# Sensing_-_Position.net
KiCad netlist of a schematic drawn in Altium Designer
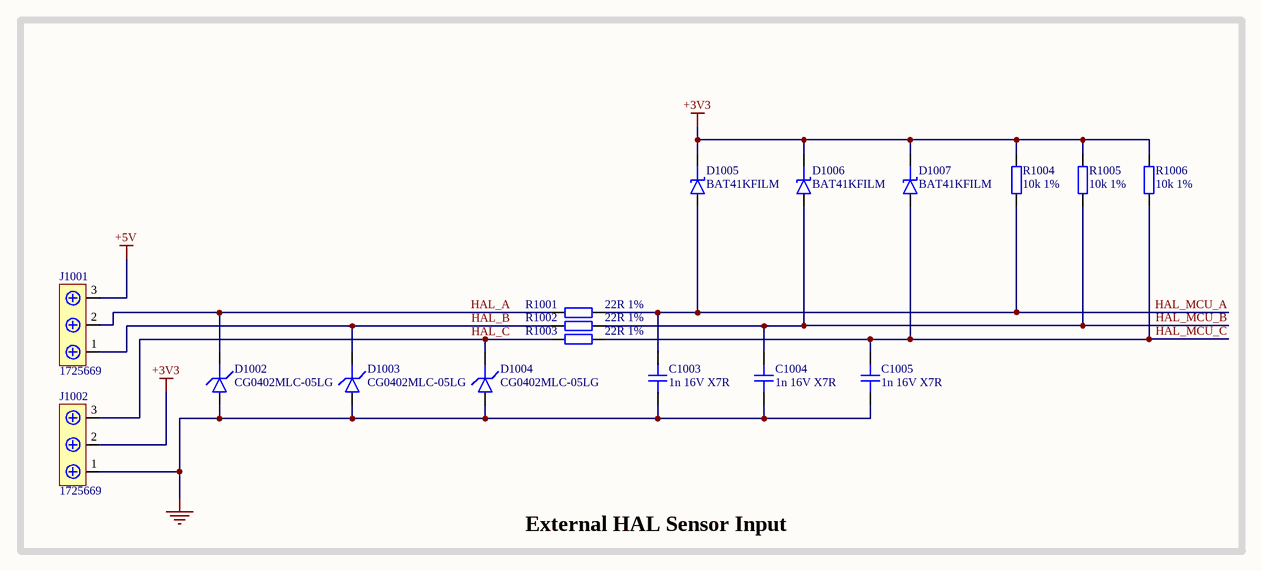
[diagram p0: Sensing - Position.SchDoc]

(export (version "E")
  (design (tool "Eeschema 10.0.6"))
  (components
    (comp (ref "C1003")
      (value "1n 16V X7R")
      (footprint "CAP_0402")
      (description "Capacitor SMD 0402")
      (fields
        (field (name "MANUFACTURER") "YAGEO")
        (field (name "MANUFACTURER PART NUMBER") "CC0402KRX7R7BB102")
      )
      (libsource (lib "Schematic-Lib-PhilsLab") (part "CAP_0402"))
    )
    (comp (ref "C1004")
      (value "1n 16V X7R")
      (footprint "CAP_0402")
      (description "Capacitor SMD 0402")
      (fields
        (field (name "MANUFACTURER") "YAGEO")
        (field (name "MANUFACTURER PART NUMBER") "CC0402KRX7R7BB102")
      )
      (libsource (lib "Schematic-Lib-PhilsLab") (part "CAP_0402"))
    )
    (comp (ref "C1005")
      (value "1n 16V X7R")
      (footprint "CAP_0402")
      (description "Capacitor SMD 0402")
      (fields
        (field (name "MANUFACTURER") "YAGEO")
        (field (name "MANUFACTURER PART NUMBER") "CC0402KRX7R7BB102")
      )
      (libsource (lib "Schematic-Lib-PhilsLab") (part "CAP_0402"))
    )
    (comp (ref "D1002")
      (value "CG0402MLC-05LG")
      (footprint "D_0402")
      (description "Diode TVS / ESD 0402")
      (fields (field (name "MANUFACTURER") "BOURNS"))
      (libsource (lib "Schematic-Lib-PhilsLab") (part "D_TVS_0402"))
    )
    (comp (ref "D1003")
      (value "CG0402MLC-05LG")
      (footprint "D_0402")
      (description "Diode TVS / ESD 0402")
      (libsource (lib "Schematic-Lib-PhilsLab") (part "D_TVS_0402"))
    )
    (comp (ref "D1004")
      (value "CG0402MLC-05LG")
      (footprint "D_0402")
      (description "Diode TVS / ESD 0402")
      (libsource (lib "Schematic-Lib-PhilsLab") (part "D_TVS_0402"))
    )
    (comp (ref "D1005")
      (value "BAT41KFILM")
      (footprint "SOD-523")
      (description "Diode Schottky SMD SOD-323")
      (fields (field (name "MANUFACTURER") "STMicroelectronics"))
      (libsource (lib "Schematic-Lib-PhilsLab") (part "D_SCHOTTKY_SOD_523"))
    )
    (comp (ref "D1006")
      (value "BAT41KFILM")
      (footprint "SOD-523")
      (description "Diode Schottky SMD SOD-323")
      (fields (field (name "MANUFACTURER") "STMicroelectronics"))
      (libsource (lib "Schematic-Lib-PhilsLab") (part "D_SCHOTTKY_SOD_523"))
    )
    (comp (ref "D1007")
      (value "BAT41KFILM")
      (footprint "SOD-523")
      (description "Diode Schottky SMD SOD-323")
      (fields (field (name "MANUFACTURER") "STMicroelectronics"))
      (libsource (lib "Schematic-Lib-PhilsLab") (part "D_SCHOTTKY_SOD_523"))
    )
    (comp (ref "J1001")
      (value "1725669")
      (footprint "1725669")
      (description "Screw Terminal Block 3 Positions 2.54mm")
      (fields (field (name "MANUFACTURER") "Phoenix"))
      (libsource (lib "Schematic-Lib") (part "1725669"))
    )
    (comp (ref "J1002")
      (value "1725669")
      (footprint "1725669")
      (description "Screw Terminal Block 3 Positions 2.54mm")
      (fields (field (name "MANUFACTURER") "Phoenix"))
      (libsource (lib "Schematic-Lib") (part "1725669"))
    )
    (comp (ref "R1001")
      (value "22R 1%")
      (footprint "RES_0402")
      (description "Resistor SMD 0402")
      (fields
        (field (name "MANUFACTURER") "PANASONIC")
        (field (name "MANUFACTURER PART NUMBER") "ERJPA2F22R0X")
      )
      (libsource (lib "Schematic-Lib-PhilsLab") (part "RES_0402"))
    )
    (comp (ref "R1002")
      (value "22R 1%")
      (footprint "RES_0402")
      (description "Resistor SMD 0402")
      (fields
        (field (name "MANUFACTURER") "PANASONIC")
        (field (name "MANUFACTURER PART NUMBER") "ERJPA2F22R0X")
      )
      (libsource (lib "Schematic-Lib-PhilsLab") (part "RES_0402"))
    )
    (comp (ref "R1003")
      (value "22R 1%")
      (footprint "RES_0402")
      (description "Resistor SMD 0402")
      (fields
        (field (name "MANUFACTURER") "PANASONIC")
        (field (name "MANUFACTURER PART NUMBER") "ERJPA2F22R0X")
      )
      (libsource (lib "Schematic-Lib-PhilsLab") (part "RES_0402"))
    )
    (comp (ref "R1004")
      (value "10k 1%")
      (footprint "RES_0402")
      (description "Resistor SMD 0402")
      (fields
        (field (name "MANUFACTURER") "PANASONIC")
        (field (name "MANUFACTURER PART NUMBER") "ERJPA2F1002X")
      )
      (libsource (lib "Schematic-Lib-PhilsLab") (part "RES_0402"))
    )
    (comp (ref "R1005")
      (value "10k 1%")
      (footprint "RES_0402")
      (description "Resistor SMD 0402")
      (fields
        (field (name "MANUFACTURER") "PANASONIC")
        (field (name "MANUFACTURER PART NUMBER") "ERJPA2F1002X")
      )
      (libsource (lib "Schematic-Lib-PhilsLab") (part "RES_0402"))
    )
    (comp (ref "R1006")
      (value "10k 1%")
      (footprint "RES_0402")
      (description "Resistor SMD 0402")
      (fields
        (field (name "MANUFACTURER") "PANASONIC")
        (field (name "MANUFACTURER PART NUMBER") "ERJPA2F1002X")
      )
      (libsource (lib "Schematic-Lib-PhilsLab") (part "RES_0402"))
    )
  )
  (nets
    (net (code "1") (name "+3V3") (class "Default")
      (node (ref "D1005") (pin "K") (pinfunction "K_K") (pintype "passive"))
      (node (ref "D1006") (pin "K") (pinfunction "K_K") (pintype "passive"))
      (node (ref "D1007") (pin "K") (pinfunction "K_K") (pintype "passive"))
      (node (ref "J1002") (pin "2") (pinfunction "2_2") (pintype "passive"))
      (node (ref "R1004") (pin "2") (pinfunction "2_2") (pintype "passive"))
      (node (ref "R1005") (pin "2") (pinfunction "2_2") (pintype "passive"))
      (node (ref "R1006") (pin "2") (pinfunction "2_2") (pintype "passive"))
    )
    (net (code "2") (name "+5V") (class "Default")
      (node (ref "J1001") (pin "3") (pinfunction "3_3") (pintype "passive"))
    )
    (net (code "3") (name "/HAL_A") (class "Default")
      (node (ref "D1002") (pin "K") (pinfunction "K_K") (pintype "passive"))
      (node (ref "J1001") (pin "2") (pinfunction "2_2") (pintype "passive"))
      (node (ref "R1001") (pin "2") (pinfunction "2_2") (pintype "passive"))
    )
    (net (code "4") (name "/HAL_B") (class "Default")
      (node (ref "D1003") (pin "K") (pinfunction "K_K") (pintype "passive"))
      (node (ref "J1001") (pin "1") (pinfunction "1_1") (pintype "passive"))
      (node (ref "R1002") (pin "2") (pinfunction "2_2") (pintype "passive"))
    )
    (net (code "5") (name "/HAL_C") (class "Default")
      (node (ref "D1004") (pin "K") (pinfunction "K_K") (pintype "passive"))
      (node (ref "J1002") (pin "3") (pinfunction "3_3") (pintype "passive"))
      (node (ref "R1003") (pin "2") (pinfunction "2_2") (pintype "passive"))
    )
    (net (code "6") (name "/HAL_MCU_A") (class "Default")
      (node (ref "C1003") (pin "2") (pinfunction "2_2") (pintype "passive"))
      (node (ref "D1005") (pin "A") (pinfunction "A_A") (pintype "passive"))
      (node (ref "R1001") (pin "1") (pinfunction "1_1") (pintype "passive"))
      (node (ref "R1004") (pin "1") (pinfunction "1_1") (pintype "passive"))
    )
    (net (code "7") (name "/HAL_MCU_B") (class "Default")
      (node (ref "C1004") (pin "2") (pinfunction "2_2") (pintype "passive"))
      (node (ref "D1006") (pin "A") (pinfunction "A_A") (pintype "passive"))
      (node (ref "R1002") (pin "1") (pinfunction "1_1") (pintype "passive"))
      (node (ref "R1005") (pin "1") (pinfunction "1_1") (pintype "passive"))
    )
    (net (code "8") (name "/HAL_MCU_C") (class "Default")
      (node (ref "C1005") (pin "2") (pinfunction "2_2") (pintype "passive"))
      (node (ref "D1007") (pin "A") (pinfunction "A_A") (pintype "passive"))
      (node (ref "R1003") (pin "1") (pinfunction "1_1") (pintype "passive"))
      (node (ref "R1006") (pin "1") (pinfunction "1_1") (pintype "passive"))
    )
    (net (code "9") (name "GND") (class "Default")
      (node (ref "C1003") (pin "1") (pinfunction "1_1") (pintype "passive"))
      (node (ref "C1004") (pin "1") (pinfunction "1_1") (pintype "passive"))
      (node (ref "C1005") (pin "1") (pinfunction "1_1") (pintype "passive"))
      (node (ref "D1002") (pin "A") (pinfunction "A_A") (pintype "passive"))
      (node (ref "D1003") (pin "A") (pinfunction "A_A") (pintype "passive"))
      (node (ref "D1004") (pin "A") (pinfunction "A_A") (pintype "passive"))
      (node (ref "J1002") (pin "1") (pinfunction "1_1") (pintype "passive"))
    )
  )
)
